# controller.net
KiCad netlist of a schematic drawn in EAGLE
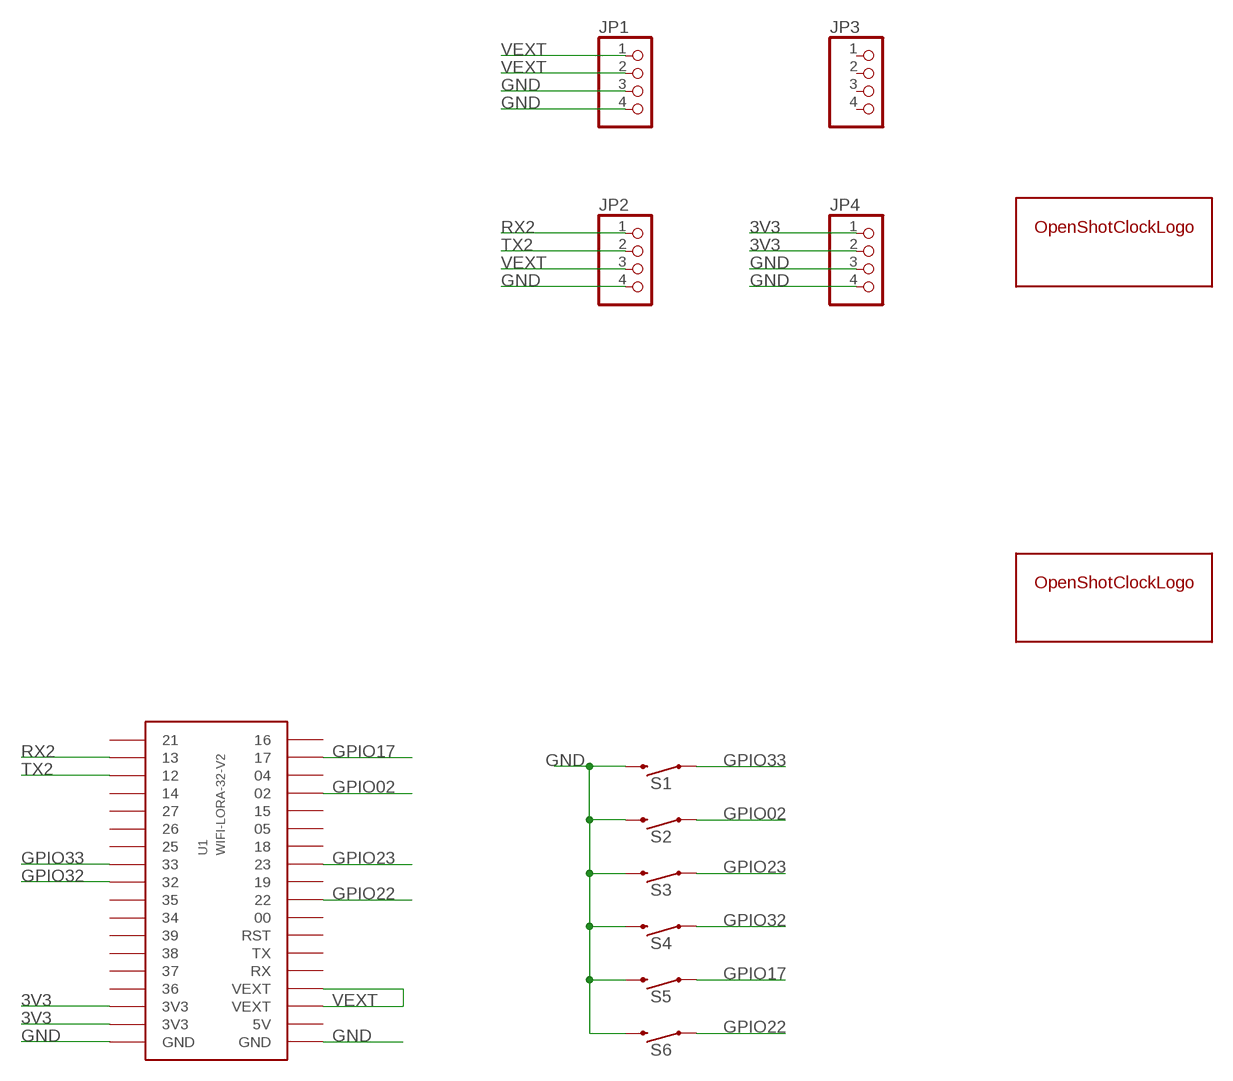
[diagram p0: schematic, sheet 1]

(export (version "E")
  (design (tool "Eeschema 10.0.6"))
  (components
    (comp (ref "JP1")
      (value "PINHD-1X4")
      (footprint "eagle-import:1X04")
      (libsource (lib "eagle-import") (part "PINHD-1X4"))
    )
    (comp (ref "JP2")
      (value "PINHD-1X4")
      (footprint "eagle-import:1X04")
      (libsource (lib "eagle-import") (part "PINHD-1X4"))
    )
    (comp (ref "JP3")
      (value "PINHD-1X4")
      (footprint "eagle-import:1X04")
      (libsource (lib "eagle-import") (part "PINHD-1X4"))
    )
    (comp (ref "JP4")
      (value "PINHD-1X4")
      (footprint "eagle-import:1X04")
      (libsource (lib "eagle-import") (part "PINHD-1X4"))
    )
    (comp (ref "S1")
      (value "MOMENTARY-SWITCH-SPST-SMD-6.0X3.5MM")
      (footprint "eagle-import:TACTILE_SWITCH_SMD_6.0X3.5MM")
      (libsource (lib "eagle-import") (part "MOMENTARY-SWITCH-SPST-SMD-6.0X3.5MM"))
    )
    (comp (ref "S2")
      (value "MOMENTARY-SWITCH-SPST-SMD-6.0X3.5MM")
      (footprint "eagle-import:TACTILE_SWITCH_SMD_6.0X3.5MM")
      (libsource (lib "eagle-import") (part "MOMENTARY-SWITCH-SPST-SMD-6.0X3.5MM"))
    )
    (comp (ref "S3")
      (value "MOMENTARY-SWITCH-SPST-SMD-6.0X3.5MM")
      (footprint "eagle-import:TACTILE_SWITCH_SMD_6.0X3.5MM")
      (libsource (lib "eagle-import") (part "MOMENTARY-SWITCH-SPST-SMD-6.0X3.5MM"))
    )
    (comp (ref "S4")
      (value "MOMENTARY-SWITCH-SPST-SMD-6.0X3.5MM")
      (footprint "eagle-import:TACTILE_SWITCH_SMD_6.0X3.5MM")
      (libsource (lib "eagle-import") (part "MOMENTARY-SWITCH-SPST-SMD-6.0X3.5MM"))
    )
    (comp (ref "S5")
      (value "MOMENTARY-SWITCH-SPST-SMD-6.0X3.5MM")
      (footprint "eagle-import:TACTILE_SWITCH_SMD_6.0X3.5MM")
      (libsource (lib "eagle-import") (part "MOMENTARY-SWITCH-SPST-SMD-6.0X3.5MM"))
    )
    (comp (ref "S6")
      (value "MOMENTARY-SWITCH-SPST-SMD-6.0X3.5MM")
      (footprint "eagle-import:TACTILE_SWITCH_SMD_6.0X3.5MM")
      (libsource (lib "eagle-import") (part "MOMENTARY-SWITCH-SPST-SMD-6.0X3.5MM"))
    )
    (comp (ref "U$2")
      (value "OPEN-SHOT-CLOCK-LOGOOSCL-SMALL")
      (footprint "eagle-import:OPEN-SHOT-CLOCK-LOGO-SMALL")
      (libsource (lib "eagle-import") (part "OPEN-SHOT-CLOCK-LOGOOSCL-SMALL"))
    )
    (comp (ref "U$5")
      (value "OPEN-SHOT-CLOCK-LOGOOSCL-SMALL")
      (footprint "eagle-import:OPEN-SHOT-CLOCK-LOGO-SMALL")
      (libsource (lib "eagle-import") (part "OPEN-SHOT-CLOCK-LOGOOSCL-SMALL"))
    )
    (comp (ref "U1")
      (value "WIFI-LORA-32-V2")
      (footprint "eagle-import:2.54MM_2X18")
      (libsource (lib "eagle-import") (part "WIFI-LORA-32-V2"))
    )
  )
  (nets
    (net (code "1") (name "/3V3") (class "Default")
      (node (ref "JP4") (pin "1") (pinfunction "1_1") (pintype "passive"))
      (node (ref "JP4") (pin "2") (pinfunction "2_2") (pintype "passive"))
      (node (ref "U1") (pin "P$34") (pinfunction "3V3_P$34") (pintype "power_in"))
      (node (ref "U1") (pin "P$35") (pinfunction "3V3_P$35") (pintype "power_in"))
    )
    (net (code "2") (name "/5V") (class "Default")
      (node (ref "U1") (pin "P$2") (pinfunction "5V_P$2") (pintype "power_in"))
    )
    (net (code "3") (name "/GND") (class "Default")
      (node (ref "JP1") (pin "3") (pinfunction "3_3") (pintype "passive"))
      (node (ref "JP1") (pin "4") (pinfunction "4_4") (pintype "passive"))
      (node (ref "JP2") (pin "4") (pinfunction "4_4") (pintype "passive"))
      (node (ref "JP4") (pin "3") (pinfunction "3_3") (pintype "passive"))
      (node (ref "JP4") (pin "4") (pinfunction "4_4") (pintype "passive"))
      (node (ref "S1") (pin "2") (pinfunction "2_2") (pintype "passive"))
      (node (ref "S2") (pin "2") (pinfunction "2_2") (pintype "passive"))
      (node (ref "S3") (pin "2") (pinfunction "2_2") (pintype "passive"))
      (node (ref "S4") (pin "2") (pinfunction "2_2") (pintype "passive"))
      (node (ref "S5") (pin "2") (pinfunction "2_2") (pintype "passive"))
      (node (ref "S6") (pin "2") (pinfunction "2_2") (pintype "passive"))
      (node (ref "U1") (pin "P$1") (pinfunction "GND_P$1") (pintype "power_in"))
      (node (ref "U1") (pin "P$36") (pinfunction "GND_P$36") (pintype "power_in"))
    )
    (net (code "4") (name "/GPIO02") (class "Default")
      (node (ref "S2") (pin "1") (pinfunction "1_1") (pintype "passive"))
      (node (ref "U1") (pin "P$15") (pinfunction "02_P$15") (pintype "bidirectional"))
    )
    (net (code "5") (name "/GPIO17") (class "Default")
      (node (ref "S5") (pin "1") (pinfunction "1_1") (pintype "passive"))
      (node (ref "U1") (pin "P$17") (pinfunction "17_P$17") (pintype "bidirectional"))
    )
    (net (code "6") (name "/GPIO22") (class "Default")
      (node (ref "S6") (pin "1") (pinfunction "1_1") (pintype "passive"))
      (node (ref "U1") (pin "P$9") (pinfunction "22_P$9") (pintype "bidirectional"))
    )
    (net (code "7") (name "/GPIO23") (class "Default")
      (node (ref "S3") (pin "1") (pinfunction "1_1") (pintype "passive"))
      (node (ref "U1") (pin "P$11") (pinfunction "23_P$11") (pintype "bidirectional"))
    )
    (net (code "8") (name "/GPIO32") (class "Default")
      (node (ref "S4") (pin "1") (pinfunction "1_1") (pintype "passive"))
      (node (ref "U1") (pin "P$27") (pinfunction "32_P$27") (pintype "bidirectional"))
    )
    (net (code "9") (name "/GPIO33") (class "Default")
      (node (ref "S1") (pin "1") (pinfunction "1_1") (pintype "passive"))
      (node (ref "U1") (pin "P$26") (pinfunction "33_P$26") (pintype "bidirectional"))
    )
    (net (code "10") (name "/RX2") (class "Default")
      (node (ref "JP2") (pin "1") (pinfunction "1_1") (pintype "passive"))
      (node (ref "U1") (pin "P$20") (pinfunction "13_P$20") (pintype "bidirectional"))
    )
    (net (code "11") (name "/TX2") (class "Default")
      (node (ref "JP2") (pin "2") (pinfunction "2_2") (pintype "passive"))
      (node (ref "U1") (pin "P$21") (pinfunction "12_P$21") (pintype "bidirectional"))
    )
    (net (code "12") (name "/VEXT") (class "Default")
      (node (ref "JP1") (pin "1") (pinfunction "1_1") (pintype "passive"))
      (node (ref "JP1") (pin "2") (pinfunction "2_2") (pintype "passive"))
      (node (ref "JP2") (pin "3") (pinfunction "3_3") (pintype "passive"))
      (node (ref "U1") (pin "P$3") (pinfunction "VEXT_P$3") (pintype "power_in"))
      (node (ref "U1") (pin "P$4") (pinfunction "VEXT_P$4") (pintype "bidirectional"))
    )
    (net (code "13") (name "unconnected-(JP3-Pad1)") (class "Default")
      (node (ref "JP3") (pin "1") (pinfunction "1_1") (pintype "passive"))
    )
    (net (code "14") (name "unconnected-(JP3-Pad2)") (class "Default")
      (node (ref "JP3") (pin "2") (pinfunction "2_2") (pintype "passive"))
    )
    (net (code "15") (name "unconnected-(JP3-Pad3)") (class "Default")
      (node (ref "JP3") (pin "3") (pinfunction "3_3") (pintype "passive"))
    )
    (net (code "16") (name "unconnected-(JP3-Pad4)") (class "Default")
      (node (ref "JP3") (pin "4") (pinfunction "4_4") (pintype "passive"))
    )
    (net (code "17") (name "unconnected-(U1-00-PadP$8)") (class "Default")
      (node (ref "U1") (pin "P$8") (pinfunction "00_P$8") (pintype "bidirectional"))
    )
    (net (code "18") (name "unconnected-(U1-04-PadP$16)") (class "Default")
      (node (ref "U1") (pin "P$16") (pinfunction "04_P$16") (pintype "bidirectional"))
    )
    (net (code "19") (name "unconnected-(U1-05-PadP$13)") (class "Default")
      (node (ref "U1") (pin "P$13") (pinfunction "05_P$13") (pintype "bidirectional"))
    )
    (net (code "20") (name "unconnected-(U1-14-PadP$22)") (class "Default")
      (node (ref "U1") (pin "P$22") (pinfunction "14_P$22") (pintype "bidirectional"))
    )
    (net (code "21") (name "unconnected-(U1-15-PadP$14)") (class "Default")
      (node (ref "U1") (pin "P$14") (pinfunction "15_P$14") (pintype "bidirectional"))
    )
    (net (code "22") (name "unconnected-(U1-16-PadP$18)") (class "Default")
      (node (ref "U1") (pin "P$18") (pinfunction "16_P$18") (pintype "bidirectional"))
    )
    (net (code "23") (name "unconnected-(U1-18-PadP$12)") (class "Default")
      (node (ref "U1") (pin "P$12") (pinfunction "18_P$12") (pintype "bidirectional"))
    )
    (net (code "24") (name "unconnected-(U1-19-PadP$10)") (class "Default")
      (node (ref "U1") (pin "P$10") (pinfunction "19_P$10") (pintype "bidirectional"))
    )
    (net (code "25") (name "unconnected-(U1-21-PadP$19)") (class "Default")
      (node (ref "U1") (pin "P$19") (pinfunction "21_P$19") (pintype "bidirectional"))
    )
    (net (code "26") (name "unconnected-(U1-25-PadP$25)") (class "Default")
      (node (ref "U1") (pin "P$25") (pinfunction "25_P$25") (pintype "bidirectional"))
    )
    (net (code "27") (name "unconnected-(U1-26-PadP$24)") (class "Default")
      (node (ref "U1") (pin "P$24") (pinfunction "26_P$24") (pintype "bidirectional"))
    )
    (net (code "28") (name "unconnected-(U1-27-PadP$23)") (class "Default")
      (node (ref "U1") (pin "P$23") (pinfunction "27_P$23") (pintype "bidirectional"))
    )
    (net (code "29") (name "unconnected-(U1-34-PadP$29)") (class "Default")
      (node (ref "U1") (pin "P$29") (pinfunction "34_P$29") (pintype "bidirectional"))
    )
    (net (code "30") (name "unconnected-(U1-35-PadP$28)") (class "Default")
      (node (ref "U1") (pin "P$28") (pinfunction "35_P$28") (pintype "bidirectional"))
    )
    (net (code "31") (name "unconnected-(U1-36-PadP$33)") (class "Default")
      (node (ref "U1") (pin "P$33") (pinfunction "36_P$33") (pintype "bidirectional"))
    )
    (net (code "32") (name "unconnected-(U1-37-PadP$32)") (class "Default")
      (node (ref "U1") (pin "P$32") (pinfunction "37_P$32") (pintype "bidirectional"))
    )
    (net (code "33") (name "unconnected-(U1-38-PadP$31)") (class "Default")
      (node (ref "U1") (pin "P$31") (pinfunction "38_P$31") (pintype "bidirectional"))
    )
    (net (code "34") (name "unconnected-(U1-39-PadP$30)") (class "Default")
      (node (ref "U1") (pin "P$30") (pinfunction "39_P$30") (pintype "bidirectional"))
    )
    (net (code "35") (name "unconnected-(U1-RST-PadP$7)") (class "Default")
      (node (ref "U1") (pin "P$7") (pinfunction "RST_P$7") (pintype "bidirectional"))
    )
    (net (code "36") (name "unconnected-(U1-RX-PadP$5)") (class "Default")
      (node (ref "U1") (pin "P$5") (pinfunction "RX_P$5") (pintype "bidirectional"))
    )
    (net (code "37") (name "unconnected-(U1-TX-PadP$6)") (class "Default")
      (node (ref "U1") (pin "P$6") (pinfunction "TX_P$6") (pintype "bidirectional"))
    )
  )
)
